# SNES_TST_Adapter_Sheet1.net
KiCad netlist of a schematic drawn in Altium Designer
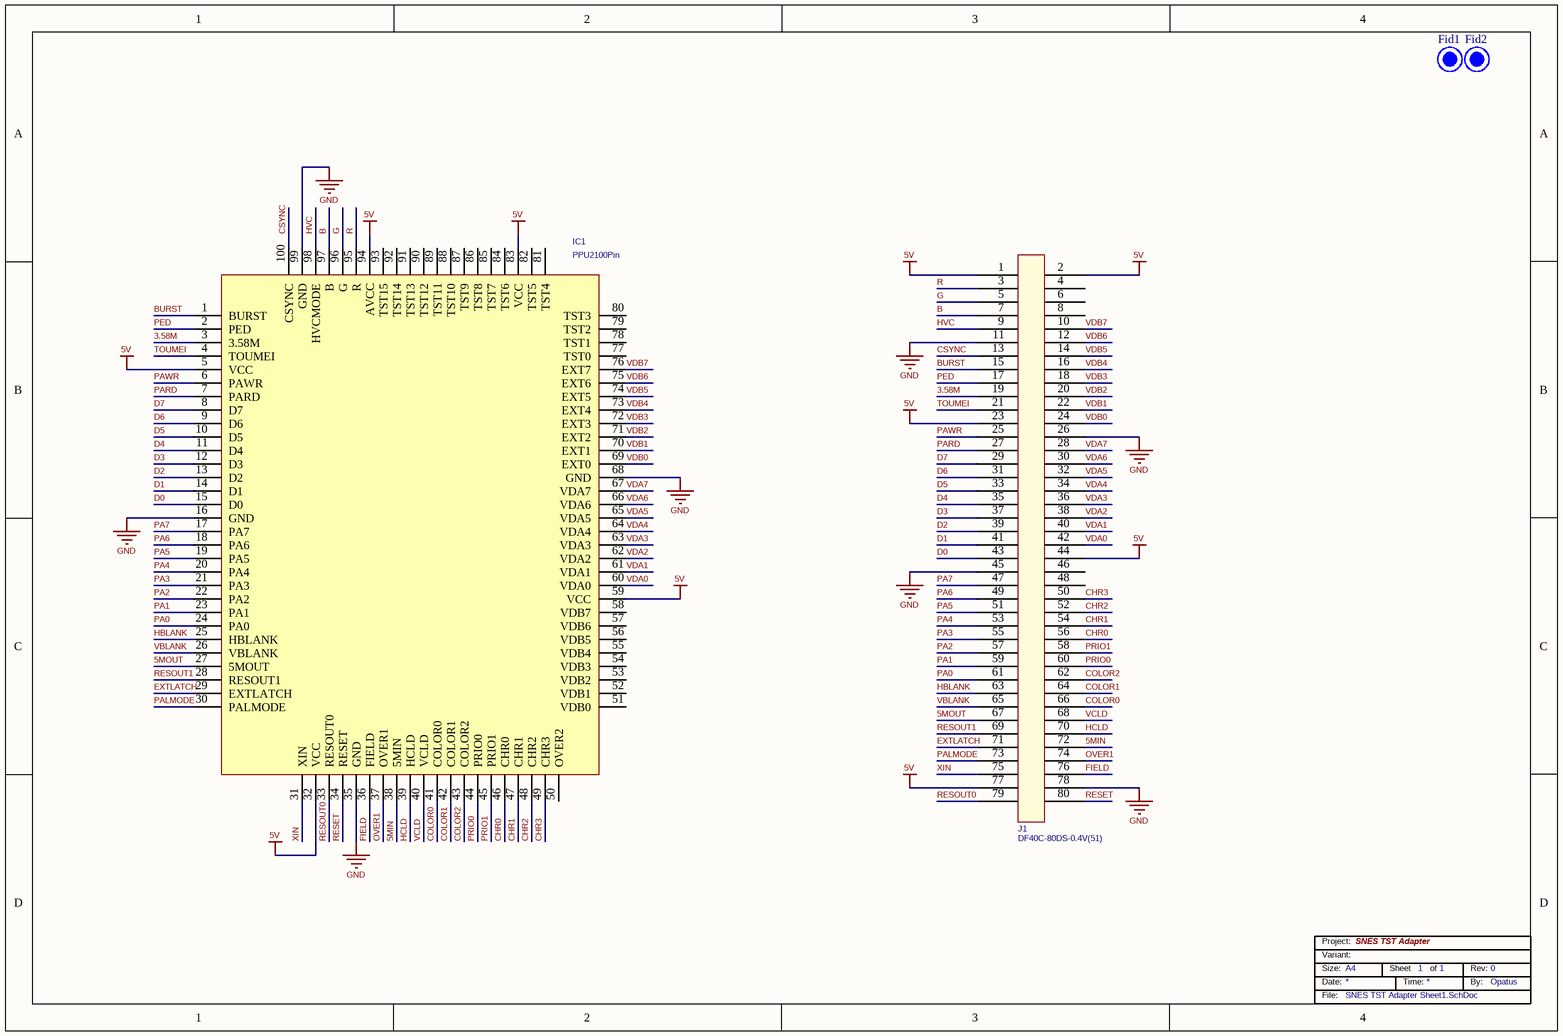
[diagram p0: SNES TST Adapter Sheet1.SchDoc]

(export (version "E")
  (design (tool "Eeschema 10.0.6"))
  (components
    (comp (ref "Fid1")
      (value "Fiducial")
      (footprint "Fiducial_1_side")
      (libsource (lib "PCB") (part "Fiducial"))
    )
    (comp (ref "Fid2")
      (value "Fiducial")
      (footprint "Fiducial_1_side")
      (libsource (lib "PCB") (part "Fiducial"))
    )
    (comp (ref "IC1")
      (value "PPU2100Pin")
      (footprint "PPU100Pin_Double")
      (description "PPU2")
      (libsource (lib "PCB") (part "PPU2100Pin"))
    )
    (comp (ref "J1")
      (value "DF40C-80DS-0.4V(51)")
      (footprint "DF40C-80DS")
      (description "80Pole Connector")
      (fields (field (name "MANUFACTURER_PART_NUMBER") "DF40C-80DS-0.4V(51)"))
      (libsource (lib "PCB") (part "Conn 80P"))
    )
  )
  (nets
    (net (code "1") (name "/3.58M") (class "Default")
      (node (ref "IC1") (pin "3") (pinfunction "3.58M_3") (pintype "passive"))
      (node (ref "J1") (pin "19") (pintype "passive"))
    )
    (net (code "2") (name "/5MIN") (class "Default")
      (node (ref "IC1") (pin "38") (pinfunction "5MIN_38") (pintype "passive"))
      (node (ref "J1") (pin "72") (pintype "passive"))
    )
    (net (code "3") (name "/5MOUT") (class "Default")
      (node (ref "IC1") (pin "27") (pinfunction "5MOUT_27") (pintype "passive"))
      (node (ref "J1") (pin "67") (pintype "passive"))
    )
    (net (code "4") (name "/B") (class "Default")
      (node (ref "IC1") (pin "97") (pinfunction "B_97") (pintype "passive"))
      (node (ref "J1") (pin "7") (pintype "passive"))
    )
    (net (code "5") (name "/BURST") (class "Default")
      (node (ref "IC1") (pin "1") (pinfunction "BURST_1") (pintype "passive"))
      (node (ref "J1") (pin "15") (pintype "passive"))
    )
    (net (code "6") (name "/CHR0") (class "Default")
      (node (ref "IC1") (pin "46") (pinfunction "CHR0_46") (pintype "passive"))
      (node (ref "J1") (pin "56") (pintype "passive"))
    )
    (net (code "7") (name "/CHR1") (class "Default")
      (node (ref "IC1") (pin "47") (pinfunction "CHR1_47") (pintype "passive"))
      (node (ref "J1") (pin "54") (pintype "passive"))
    )
    (net (code "8") (name "/CHR2") (class "Default")
      (node (ref "IC1") (pin "48") (pinfunction "CHR2_48") (pintype "passive"))
      (node (ref "J1") (pin "52") (pintype "passive"))
    )
    (net (code "9") (name "/CHR3") (class "Default")
      (node (ref "IC1") (pin "49") (pinfunction "CHR3_49") (pintype "passive"))
      (node (ref "J1") (pin "50") (pintype "passive"))
    )
    (net (code "10") (name "/COLOR0") (class "Default")
      (node (ref "IC1") (pin "41") (pinfunction "COLOR0_41") (pintype "passive"))
      (node (ref "J1") (pin "66") (pintype "passive"))
    )
    (net (code "11") (name "/COLOR1") (class "Default")
      (node (ref "IC1") (pin "42") (pinfunction "COLOR1_42") (pintype "passive"))
      (node (ref "J1") (pin "64") (pintype "passive"))
    )
    (net (code "12") (name "/COLOR2") (class "Default")
      (node (ref "IC1") (pin "43") (pinfunction "COLOR2_43") (pintype "passive"))
      (node (ref "J1") (pin "62") (pintype "passive"))
    )
    (net (code "13") (name "/CSYNC") (class "Default")
      (node (ref "IC1") (pin "100") (pinfunction "CSYNC_100") (pintype "passive"))
      (node (ref "J1") (pin "13") (pintype "passive"))
    )
    (net (code "14") (name "/D0") (class "Default")
      (node (ref "IC1") (pin "15") (pinfunction "D0_15") (pintype "passive"))
      (node (ref "J1") (pin "43") (pintype "passive"))
    )
    (net (code "15") (name "/D1") (class "Default")
      (node (ref "IC1") (pin "14") (pinfunction "D1_14") (pintype "passive"))
      (node (ref "J1") (pin "41") (pintype "passive"))
    )
    (net (code "16") (name "/D2") (class "Default")
      (node (ref "IC1") (pin "13") (pinfunction "D2_13") (pintype "passive"))
      (node (ref "J1") (pin "39") (pintype "passive"))
    )
    (net (code "17") (name "/D3") (class "Default")
      (node (ref "IC1") (pin "12") (pinfunction "D3_12") (pintype "passive"))
      (node (ref "J1") (pin "37") (pintype "passive"))
    )
    (net (code "18") (name "/D4") (class "Default")
      (node (ref "IC1") (pin "11") (pinfunction "D4_11") (pintype "passive"))
      (node (ref "J1") (pin "35") (pintype "passive"))
    )
    (net (code "19") (name "/D5") (class "Default")
      (node (ref "IC1") (pin "10") (pinfunction "D5_10") (pintype "passive"))
      (node (ref "J1") (pin "33") (pintype "passive"))
    )
    (net (code "20") (name "/D6") (class "Default")
      (node (ref "IC1") (pin "9") (pinfunction "D6_9") (pintype "passive"))
      (node (ref "J1") (pin "31") (pintype "passive"))
    )
    (net (code "21") (name "/D7") (class "Default")
      (node (ref "IC1") (pin "8") (pinfunction "D7_8") (pintype "passive"))
      (node (ref "J1") (pin "29") (pintype "passive"))
    )
    (net (code "22") (name "/EXTLATCH") (class "Default")
      (node (ref "IC1") (pin "29") (pinfunction "EXTLATCH_29") (pintype "passive"))
      (node (ref "J1") (pin "71") (pintype "passive"))
    )
    (net (code "23") (name "/FIELD") (class "Default")
      (node (ref "IC1") (pin "36") (pinfunction "FIELD_36") (pintype "passive"))
      (node (ref "J1") (pin "76") (pintype "passive"))
    )
    (net (code "24") (name "/G") (class "Default")
      (node (ref "IC1") (pin "96") (pinfunction "G_96") (pintype "passive"))
      (node (ref "J1") (pin "5") (pintype "passive"))
    )
    (net (code "25") (name "/HBLANK") (class "Default")
      (node (ref "IC1") (pin "25") (pinfunction "HBLANK_25") (pintype "passive"))
      (node (ref "J1") (pin "63") (pintype "passive"))
    )
    (net (code "26") (name "/HCLD") (class "Default")
      (node (ref "IC1") (pin "39") (pinfunction "HCLD_39") (pintype "passive"))
      (node (ref "J1") (pin "70") (pintype "passive"))
    )
    (net (code "27") (name "/HVC") (class "Default")
      (node (ref "IC1") (pin "98") (pinfunction "HVCMODE_98") (pintype "passive"))
      (node (ref "J1") (pin "9") (pintype "passive"))
    )
    (net (code "28") (name "/OVER1") (class "Default")
      (node (ref "IC1") (pin "37") (pinfunction "OVER1_37") (pintype "passive"))
      (node (ref "J1") (pin "74") (pintype "passive"))
    )
    (net (code "29") (name "/PA0") (class "Default")
      (node (ref "IC1") (pin "24") (pinfunction "PA0_24") (pintype "passive"))
      (node (ref "J1") (pin "61") (pintype "passive"))
    )
    (net (code "30") (name "/PA1") (class "Default")
      (node (ref "IC1") (pin "23") (pinfunction "PA1_23") (pintype "passive"))
      (node (ref "J1") (pin "59") (pintype "passive"))
    )
    (net (code "31") (name "/PA2") (class "Default")
      (node (ref "IC1") (pin "22") (pinfunction "PA2_22") (pintype "passive"))
      (node (ref "J1") (pin "57") (pintype "passive"))
    )
    (net (code "32") (name "/PA3") (class "Default")
      (node (ref "IC1") (pin "21") (pinfunction "PA3_21") (pintype "passive"))
      (node (ref "J1") (pin "55") (pintype "passive"))
    )
    (net (code "33") (name "/PA4") (class "Default")
      (node (ref "IC1") (pin "20") (pinfunction "PA4_20") (pintype "passive"))
      (node (ref "J1") (pin "53") (pintype "passive"))
    )
    (net (code "34") (name "/PA5") (class "Default")
      (node (ref "IC1") (pin "19") (pinfunction "PA5_19") (pintype "passive"))
      (node (ref "J1") (pin "51") (pintype "passive"))
    )
    (net (code "35") (name "/PA6") (class "Default")
      (node (ref "IC1") (pin "18") (pinfunction "PA6_18") (pintype "passive"))
      (node (ref "J1") (pin "49") (pintype "passive"))
    )
    (net (code "36") (name "/PA7") (class "Default")
      (node (ref "IC1") (pin "17") (pinfunction "PA7_17") (pintype "passive"))
      (node (ref "J1") (pin "47") (pintype "passive"))
    )
    (net (code "37") (name "/PALMODE") (class "Default")
      (node (ref "IC1") (pin "30") (pinfunction "PALMODE_30") (pintype "passive"))
      (node (ref "J1") (pin "73") (pintype "passive"))
    )
    (net (code "38") (name "/PARD") (class "Default")
      (node (ref "IC1") (pin "7") (pinfunction "PARD_7") (pintype "passive"))
      (node (ref "J1") (pin "27") (pintype "passive"))
    )
    (net (code "39") (name "/PAWR") (class "Default")
      (node (ref "IC1") (pin "6") (pinfunction "PAWR_6") (pintype "passive"))
      (node (ref "J1") (pin "25") (pintype "passive"))
    )
    (net (code "40") (name "/PED") (class "Default")
      (node (ref "IC1") (pin "2") (pinfunction "PED_2") (pintype "passive"))
      (node (ref "J1") (pin "17") (pintype "passive"))
    )
    (net (code "41") (name "/PRIO0") (class "Default")
      (node (ref "IC1") (pin "44") (pinfunction "PRIO0_44") (pintype "passive"))
      (node (ref "J1") (pin "60") (pintype "passive"))
    )
    (net (code "42") (name "/PRIO1") (class "Default")
      (node (ref "IC1") (pin "45") (pinfunction "PRIO1_45") (pintype "passive"))
      (node (ref "J1") (pin "58") (pintype "passive"))
    )
    (net (code "43") (name "/R") (class "Default")
      (node (ref "IC1") (pin "95") (pinfunction "R_95") (pintype "passive"))
      (node (ref "J1") (pin "3") (pintype "passive"))
    )
    (net (code "44") (name "/RESET") (class "Default")
      (node (ref "IC1") (pin "34") (pinfunction "RESET_34") (pintype "passive"))
      (node (ref "J1") (pin "80") (pintype "passive"))
    )
    (net (code "45") (name "/RESOUT0") (class "Default")
      (node (ref "IC1") (pin "33") (pinfunction "RESOUT0_33") (pintype "passive"))
      (node (ref "J1") (pin "79") (pintype "passive"))
    )
    (net (code "46") (name "/RESOUT1") (class "Default")
      (node (ref "IC1") (pin "28") (pinfunction "RESOUT1_28") (pintype "passive"))
      (node (ref "J1") (pin "69") (pintype "passive"))
    )
    (net (code "47") (name "/TOUMEI") (class "Default")
      (node (ref "IC1") (pin "4") (pinfunction "TOUMEI_4") (pintype "passive"))
      (node (ref "J1") (pin "21") (pintype "passive"))
    )
    (net (code "48") (name "/VBLANK") (class "Default")
      (node (ref "IC1") (pin "26") (pinfunction "VBLANK_26") (pintype "passive"))
      (node (ref "J1") (pin "65") (pintype "passive"))
    )
    (net (code "49") (name "/VCLD") (class "Default")
      (node (ref "IC1") (pin "40") (pinfunction "VCLD_40") (pintype "passive"))
      (node (ref "J1") (pin "68") (pintype "passive"))
    )
    (net (code "50") (name "/VDA0") (class "Default")
      (node (ref "IC1") (pin "60") (pinfunction "VDA0_60") (pintype "passive"))
      (node (ref "J1") (pin "42") (pintype "passive"))
    )
    (net (code "51") (name "/VDA1") (class "Default")
      (node (ref "IC1") (pin "61") (pinfunction "VDA1_61") (pintype "passive"))
      (node (ref "J1") (pin "40") (pintype "passive"))
    )
    (net (code "52") (name "/VDA2") (class "Default")
      (node (ref "IC1") (pin "62") (pinfunction "VDA2_62") (pintype "passive"))
      (node (ref "J1") (pin "38") (pintype "passive"))
    )
    (net (code "53") (name "/VDA3") (class "Default")
      (node (ref "IC1") (pin "63") (pinfunction "VDA3_63") (pintype "passive"))
      (node (ref "J1") (pin "36") (pintype "passive"))
    )
    (net (code "54") (name "/VDA4") (class "Default")
      (node (ref "IC1") (pin "64") (pinfunction "VDA4_64") (pintype "passive"))
      (node (ref "J1") (pin "34") (pintype "passive"))
    )
    (net (code "55") (name "/VDA5") (class "Default")
      (node (ref "IC1") (pin "65") (pinfunction "VDA5_65") (pintype "passive"))
      (node (ref "J1") (pin "32") (pintype "passive"))
    )
    (net (code "56") (name "/VDA6") (class "Default")
      (node (ref "IC1") (pin "66") (pinfunction "VDA6_66") (pintype "passive"))
      (node (ref "J1") (pin "30") (pintype "passive"))
    )
    (net (code "57") (name "/VDA7") (class "Default")
      (node (ref "IC1") (pin "67") (pinfunction "VDA7_67") (pintype "passive"))
      (node (ref "J1") (pin "28") (pintype "passive"))
    )
    (net (code "58") (name "/VDB0") (class "Default")
      (node (ref "IC1") (pin "69") (pinfunction "EXT0_69") (pintype "passive"))
      (node (ref "J1") (pin "24") (pintype "passive"))
    )
    (net (code "59") (name "/VDB1") (class "Default")
      (node (ref "IC1") (pin "70") (pinfunction "EXT1_70") (pintype "passive"))
      (node (ref "J1") (pin "22") (pintype "passive"))
    )
    (net (code "60") (name "/VDB2") (class "Default")
      (node (ref "IC1") (pin "71") (pinfunction "EXT2_71") (pintype "passive"))
      (node (ref "J1") (pin "20") (pintype "passive"))
    )
    (net (code "61") (name "/VDB3") (class "Default")
      (node (ref "IC1") (pin "72") (pinfunction "EXT3_72") (pintype "passive"))
      (node (ref "J1") (pin "18") (pintype "passive"))
    )
    (net (code "62") (name "/VDB4") (class "Default")
      (node (ref "IC1") (pin "73") (pinfunction "EXT4_73") (pintype "passive"))
      (node (ref "J1") (pin "16") (pintype "passive"))
    )
    (net (code "63") (name "/VDB5") (class "Default")
      (node (ref "IC1") (pin "74") (pinfunction "EXT5_74") (pintype "passive"))
      (node (ref "J1") (pin "14") (pintype "passive"))
    )
    (net (code "64") (name "/VDB6") (class "Default")
      (node (ref "IC1") (pin "75") (pinfunction "EXT6_75") (pintype "passive"))
      (node (ref "J1") (pin "12") (pintype "passive"))
    )
    (net (code "65") (name "/VDB7") (class "Default")
      (node (ref "IC1") (pin "76") (pinfunction "EXT7_76") (pintype "passive"))
      (node (ref "J1") (pin "10") (pintype "passive"))
    )
    (net (code "66") (name "/XIN") (class "Default")
      (node (ref "IC1") (pin "31") (pinfunction "XIN_31") (pintype "passive"))
      (node (ref "J1") (pin "75") (pintype "passive"))
    )
    (net (code "67") (name "5V") (class "Default")
      (node (ref "IC1") (pin "32") (pinfunction "VCC_32") (pintype "passive"))
      (node (ref "IC1") (pin "5") (pinfunction "VCC_5") (pintype "passive"))
      (node (ref "IC1") (pin "59") (pinfunction "VCC_59") (pintype "passive"))
      (node (ref "IC1") (pin "83") (pinfunction "VCC_83") (pintype "passive"))
      (node (ref "IC1") (pin "94") (pinfunction "AVCC_94") (pintype "passive"))
      (node (ref "J1") (pin "1") (pintype "passive"))
      (node (ref "J1") (pin "2") (pintype "passive"))
      (node (ref "J1") (pin "23") (pintype "passive"))
      (node (ref "J1") (pin "44") (pintype "passive"))
      (node (ref "J1") (pin "77") (pintype "passive"))
    )
    (net (code "68") (name "GND") (class "Default")
      (node (ref "IC1") (pin "16") (pinfunction "GND_16") (pintype "passive"))
      (node (ref "IC1") (pin "35") (pinfunction "GND_35") (pintype "passive"))
      (node (ref "IC1") (pin "68") (pinfunction "GND_68") (pintype "passive"))
      (node (ref "IC1") (pin "99") (pinfunction "GND_99") (pintype "passive"))
      (node (ref "J1") (pin "11") (pintype "passive"))
      (node (ref "J1") (pin "26") (pintype "passive"))
      (node (ref "J1") (pin "45") (pintype "passive"))
      (node (ref "J1") (pin "78") (pintype "passive"))
    )
    (net (code "69") (name "unconnected-(IC1-OVER2-Pad50)") (class "Default")
      (node (ref "IC1") (pin "50") (pinfunction "OVER2_50") (pintype "passive"))
    )
    (net (code "70") (name "unconnected-(IC1-TST0-Pad77)") (class "Default")
      (node (ref "IC1") (pin "77") (pinfunction "TST0_77") (pintype "passive"))
    )
    (net (code "71") (name "unconnected-(IC1-TST1-Pad78)") (class "Default")
      (node (ref "IC1") (pin "78") (pinfunction "TST1_78") (pintype "passive"))
    )
    (net (code "72") (name "unconnected-(IC1-TST2-Pad79)") (class "Default")
      (node (ref "IC1") (pin "79") (pinfunction "TST2_79") (pintype "passive"))
    )
    (net (code "73") (name "unconnected-(IC1-TST3-Pad80)") (class "Default")
      (node (ref "IC1") (pin "80") (pinfunction "TST3_80") (pintype "passive"))
    )
    (net (code "74") (name "unconnected-(IC1-TST4-Pad81)") (class "Default")
      (node (ref "IC1") (pin "81") (pinfunction "TST4_81") (pintype "passive"))
    )
    (net (code "75") (name "unconnected-(IC1-TST5-Pad82)") (class "Default")
      (node (ref "IC1") (pin "82") (pinfunction "TST5_82") (pintype "passive"))
    )
    (net (code "76") (name "unconnected-(IC1-TST6-Pad84)") (class "Default")
      (node (ref "IC1") (pin "84") (pinfunction "TST6_84") (pintype "passive"))
    )
    (net (code "77") (name "unconnected-(IC1-TST7-Pad85)") (class "Default")
      (node (ref "IC1") (pin "85") (pinfunction "TST7_85") (pintype "passive"))
    )
    (net (code "78") (name "unconnected-(IC1-TST8-Pad86)") (class "Default")
      (node (ref "IC1") (pin "86") (pinfunction "TST8_86") (pintype "passive"))
    )
    (net (code "79") (name "unconnected-(IC1-TST9-Pad87)") (class "Default")
      (node (ref "IC1") (pin "87") (pinfunction "TST9_87") (pintype "passive"))
    )
    (net (code "80") (name "unconnected-(IC1-TST10-Pad88)") (class "Default")
      (node (ref "IC1") (pin "88") (pinfunction "TST10_88") (pintype "passive"))
    )
    (net (code "81") (name "unconnected-(IC1-TST11-Pad89)") (class "Default")
      (node (ref "IC1") (pin "89") (pinfunction "TST11_89") (pintype "passive"))
    )
    (net (code "82") (name "unconnected-(IC1-TST12-Pad90)") (class "Default")
      (node (ref "IC1") (pin "90") (pinfunction "TST12_90") (pintype "passive"))
    )
    (net (code "83") (name "unconnected-(IC1-TST13-Pad91)") (class "Default")
      (node (ref "IC1") (pin "91") (pinfunction "TST13_91") (pintype "passive"))
    )
    (net (code "84") (name "unconnected-(IC1-TST14-Pad92)") (class "Default")
      (node (ref "IC1") (pin "92") (pinfunction "TST14_92") (pintype "passive"))
    )
    (net (code "85") (name "unconnected-(IC1-TST15-Pad93)") (class "Default")
      (node (ref "IC1") (pin "93") (pinfunction "TST15_93") (pintype "passive"))
    )
    (net (code "86") (name "unconnected-(IC1-VDB0-Pad51)") (class "Default")
      (node (ref "IC1") (pin "51") (pinfunction "VDB0_51") (pintype "passive"))
    )
    (net (code "87") (name "unconnected-(IC1-VDB1-Pad52)") (class "Default")
      (node (ref "IC1") (pin "52") (pinfunction "VDB1_52") (pintype "passive"))
    )
    (net (code "88") (name "unconnected-(IC1-VDB2-Pad53)") (class "Default")
      (node (ref "IC1") (pin "53") (pinfunction "VDB2_53") (pintype "passive"))
    )
    (net (code "89") (name "unconnected-(IC1-VDB3-Pad54)") (class "Default")
      (node (ref "IC1") (pin "54") (pinfunction "VDB3_54") (pintype "passive"))
    )
    (net (code "90") (name "unconnected-(IC1-VDB4-Pad55)") (class "Default")
      (node (ref "IC1") (pin "55") (pinfunction "VDB4_55") (pintype "passive"))
    )
    (net (code "91") (name "unconnected-(IC1-VDB5-Pad56)") (class "Default")
      (node (ref "IC1") (pin "56") (pinfunction "VDB5_56") (pintype "passive"))
    )
    (net (code "92") (name "unconnected-(IC1-VDB6-Pad57)") (class "Default")
      (node (ref "IC1") (pin "57") (pinfunction "VDB6_57") (pintype "passive"))
    )
    (net (code "93") (name "unconnected-(IC1-VDB7-Pad58)") (class "Default")
      (node (ref "IC1") (pin "58") (pinfunction "VDB7_58") (pintype "passive"))
    )
    (net (code "94") (name "unconnected-(J1-Pad4)") (class "Default")
      (node (ref "J1") (pin "4") (pintype "passive"))
    )
    (net (code "95") (name "unconnected-(J1-Pad6)") (class "Default")
      (node (ref "J1") (pin "6") (pintype "passive"))
    )
    (net (code "96") (name "unconnected-(J1-Pad8)") (class "Default")
      (node (ref "J1") (pin "8") (pintype "passive"))
    )
    (net (code "97") (name "unconnected-(J1-Pad46)") (class "Default")
      (node (ref "J1") (pin "46") (pintype "passive"))
    )
    (net (code "98") (name "unconnected-(J1-Pad48)") (class "Default")
      (node (ref "J1") (pin "48") (pintype "passive"))
    )
  )
)
